# FPGA.net
KiCad netlist of a schematic drawn in Altium Designer
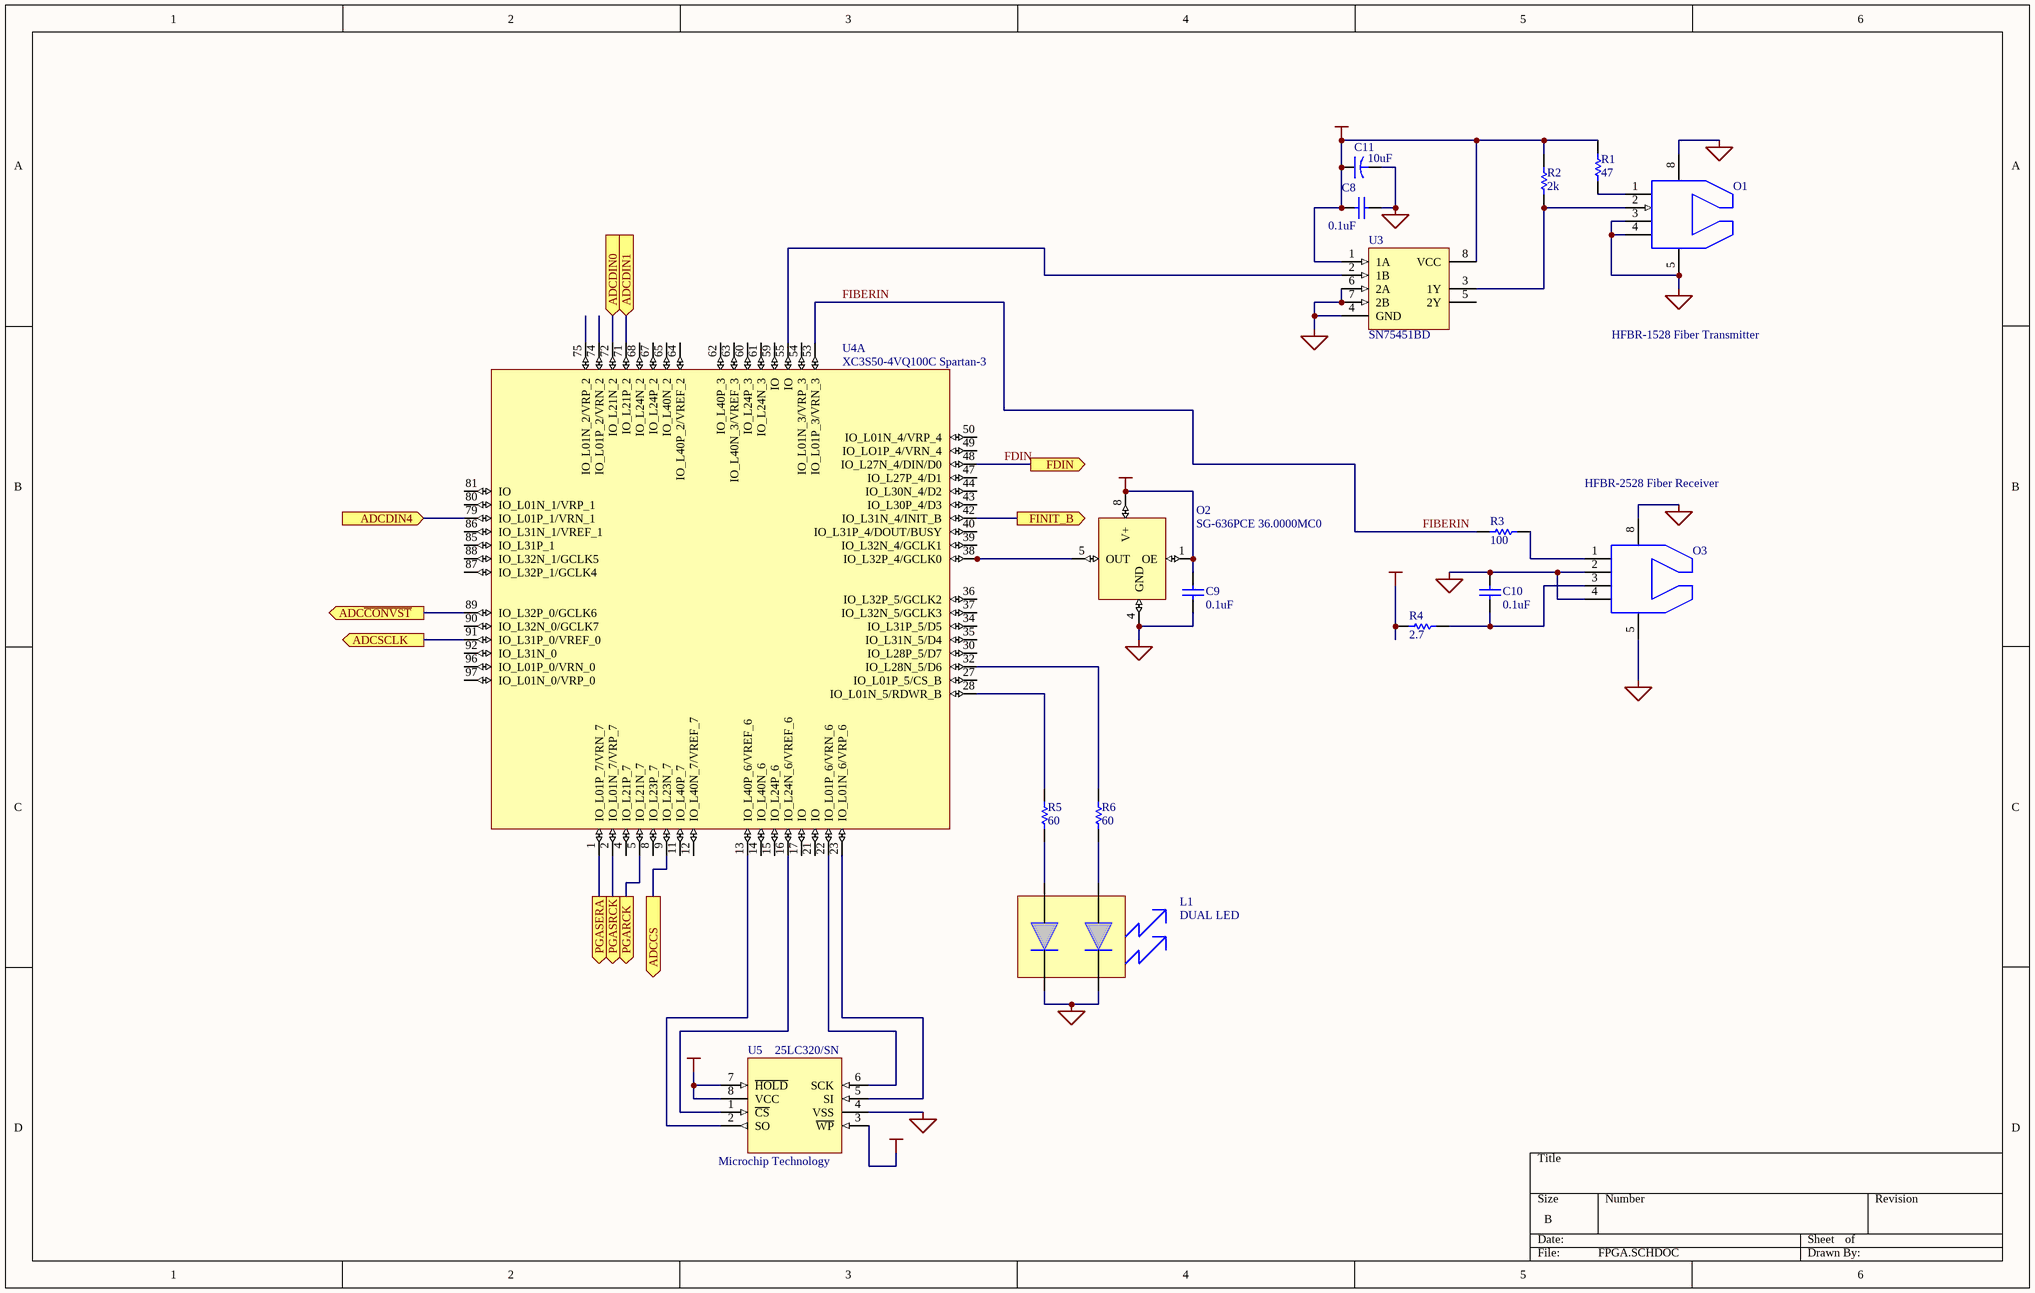
[diagram p0: FPGA.SCHDOC]

(export (version "E")
  (design (tool "Eeschema 10.0.6"))
  (components
    (comp (ref "C8")
      (value "0.1uF")
      (footprint "CC1608-0603")
      (description "Capacitor")
      (fields
        (field (name "MANUFACTURER") "Generic Components")
        (field (name "Comment") "Cap")
        (field (name "PUBLISHER") "Altium Limited")
      )
      (libsource (lib "Miscellaneous Devices") (part "Cap"))
    )
    (comp (ref "C9")
      (value "0.1uF")
      (footprint "CC1608-0603")
      (description "Capacitor")
      (fields
        (field (name "MANUFACTURER") "Generic Components")
        (field (name "Comment") "Cap")
        (field (name "PUBLISHER") "Altium Limited")
      )
      (libsource (lib "Miscellaneous Devices") (part "Cap"))
    )
    (comp (ref "C10")
      (value "0.1uF")
      (footprint "CC1608-0603")
      (description "Capacitor")
      (fields
        (field (name "MANUFACTURER") "Generic Components")
        (field (name "Comment") "Cap")
        (field (name "PUBLISHER") "Altium Limited")
      )
      (libsource (lib "Miscellaneous Devices") (part "Cap"))
    )
    (comp (ref "C11")
      (value "10uF")
      (footprint "TC3528-1411")
      (description "Capacitor")
      (fields (field (name "MANUFACTURER") "Generic Components") (field (name "PUBLISHER") "Altium Limited"))
      (libsource (lib "Miscellaneous Devices") (part "Cap2"))
    )
    (comp (ref "L1")
      (value "DUAL LED")
      (footprint "LUMEX DUAL RT-ANG LED")
      (libsource (lib "parts") (part "DUAL LED"))
    )
    (comp (ref "O1")
      (value "HFBR-1528 Fiber Transmitter")
      (footprint "HPVL")
      (description "Low-cost fiber transmitter")
      (libsource (lib "parts") (part "HFBR-1528"))
    )
    (comp (ref "O2")
      (value "SG-636PCE 36.0000MC0")
      (footprint "SG636PCE")
      (description "Epson CMOS/TTL Oscillator")
      (libsource (lib "parts") (part "SG-636PCE"))
    )
    (comp (ref "O3")
      (value "HFBR-2528 Fiber Receiver")
      (footprint "HPVL")
      (description "Low-cost fiber receiver")
      (libsource (lib "parts") (part "HFBR-2528"))
    )
    (comp (ref "R1")
      (value "47")
      (footprint "CC1608-0603")
      (description "Resistor")
      (fields
        (field (name "MANUFACTURER") "Generic Components")
        (field (name "Comment") "Res1")
        (field (name "PUBLISHER") "Altium Limited")
      )
      (libsource (lib "Miscellaneous Devices") (part "Res1"))
    )
    (comp (ref "R2")
      (value "2k")
      (footprint "CC1608-0603")
      (description "Resistor")
      (fields
        (field (name "MANUFACTURER") "Generic Components")
        (field (name "Comment") "Res1")
        (field (name "PUBLISHER") "Altium Limited")
      )
      (libsource (lib "Miscellaneous Devices") (part "Res1"))
    )
    (comp (ref "R3")
      (value "100")
      (footprint "CC1608-0603")
      (description "Resistor")
      (fields
        (field (name "MANUFACTURER") "Generic Components")
        (field (name "Comment") "Res1")
        (field (name "PUBLISHER") "Altium Limited")
      )
      (libsource (lib "Miscellaneous Devices") (part "Res1"))
    )
    (comp (ref "R4")
      (value "2.7")
      (footprint "CC1608-0603")
      (description "Resistor")
      (fields
        (field (name "MANUFACTURER") "Generic Components")
        (field (name "Comment") "Res1")
        (field (name "PUBLISHER") "Altium Limited")
      )
      (libsource (lib "Miscellaneous Devices") (part "Res1"))
    )
    (comp (ref "R5")
      (value "60")
      (footprint "CC1608-0603")
      (description "Resistor")
      (fields
        (field (name "MANUFACTURER") "Generic Components")
        (field (name "Comment") "Res1")
        (field (name "PUBLISHER") "Altium Limited")
      )
      (libsource (lib "Miscellaneous Devices") (part "Res1"))
    )
    (comp (ref "R6")
      (value "60")
      (footprint "CC1608-0603")
      (description "Resistor")
      (fields
        (field (name "MANUFACTURER") "Generic Components")
        (field (name "Comment") "Res1")
        (field (name "PUBLISHER") "Altium Limited")
      )
      (libsource (lib "Miscellaneous Devices") (part "Res1"))
    )
    (comp (ref "U3")
      (value "SN75451BD")
      (footprint "SO-G8/E2.5")
      (description "Dual Peripheral Driver")
      (fields (field (name "MANUFACTURER") "Texas Instruments") (field (name "PUBLISHER") "Altium Limited"))
      (libsource (lib "TI Interface Peripheral Driver") (part "SN75451BD"))
    )
    (comp (ref "U4")
      (value "XC3S50-4VQ100C Spartan-3")
      (footprint "F-QFP14X14-G100/N")
      (description "Xilinx Spartan-3 VQ100")
      (libsource (lib "parts") (part "XC3S50-4VQ100C"))
    )
    (comp (ref "U5")
      (value "25LC320/SN")
      (footprint "SO-G8/E2.9")
      (description "32k SPI Bus Serial EEPROM")
      (fields (field (name "VENDOR") "Microchip Technology"))
      (libsource (lib "parts") (part "25LC320-SOIC"))
    )
  )
  (nets
    (net (code "1") (name "+5VCC") (class "Default")
      (node (ref "C11") (pin "1") (pinfunction "1_1") (pintype "passive"))
      (node (ref "C8") (pin "1") (pinfunction "1_1") (pintype "passive"))
      (node (ref "R1") (pin "2") (pinfunction "2_2") (pintype "passive"))
      (node (ref "R2") (pin "2") (pinfunction "2_2") (pintype "passive"))
      (node (ref "R4") (pin "1") (pinfunction "1_1") (pintype "passive"))
      (node (ref "U3") (pin "1") (pinfunction "1A_1") (pintype "input"))
      (node (ref "U3") (pin "8") (pinfunction "VCC_8") (pintype "power_in"))
    )
    (net (code "2") (name "/ADCCS") (class "Default")
      (node (ref "U4") (pin "9") (pinfunction "IO_L23N_7_9") (pintype "bidirectional"))
    )
    (net (code "3") (name "/ADCDIN0") (class "Default")
      (node (ref "U4") (pin "72") (pinfunction "IO_L21N_2_72") (pintype "bidirectional"))
    )
    (net (code "4") (name "/ADCDIN1") (class "Default")
      (node (ref "U4") (pin "71") (pinfunction "IO_L21P_2_71") (pintype "bidirectional"))
    )
    (net (code "5") (name "/ADCDIN4") (class "Default")
      (node (ref "U4") (pin "79") (pinfunction "IO_L01P_1/VRN_1_79") (pintype "bidirectional"))
    )
    (net (code "6") (name "/ADCSCLK") (class "Default")
      (node (ref "U4") (pin "91") (pinfunction "IO_L31P_0/VREF_0_91") (pintype "bidirectional"))
    )
    (net (code "7") (name "/ADC~{CONVST}") (class "Default")
      (node (ref "U4") (pin "89") (pinfunction "IO_L32P_0/GCLK6_89") (pintype "bidirectional"))
    )
    (net (code "8") (name "/FDIN") (class "Default")
      (node (ref "U4") (pin "48") (pinfunction "IO_L27N_4/DIN/D0_48") (pintype "bidirectional"))
    )
    (net (code "9") (name "/FIBERIN") (class "Default")
      (node (ref "R3") (pin "1") (pinfunction "1_1") (pintype "passive"))
      (node (ref "U4") (pin "53") (pinfunction "IO_L01P_3/VRN_3_53") (pintype "bidirectional"))
    )
    (net (code "10") (name "/FINIT_B") (class "Default")
      (node (ref "U4") (pin "42") (pinfunction "IO_L31N_4/INIT_B_42") (pintype "bidirectional"))
    )
    (net (code "11") (name "/PGARCK") (class "Default")
      (node (ref "U4") (pin "5") (pinfunction "IO_L21N_7_5") (pintype "bidirectional"))
    )
    (net (code "12") (name "/PGASERA") (class "Default")
      (node (ref "U4") (pin "1") (pinfunction "IO_L01P_7/VRN_7_1") (pintype "bidirectional"))
    )
    (net (code "13") (name "/PGASRCK") (class "Default")
      (node (ref "U4") (pin "2") (pinfunction "IO_L01N_7/VRP_7_2") (pintype "bidirectional"))
    )
    (net (code "14") (name "GND") (class "Default")
      (node (ref "C10") (pin "2") (pinfunction "2_2") (pintype "passive"))
      (node (ref "C11") (pin "2") (pinfunction "2_2") (pintype "passive"))
      (node (ref "C8") (pin "2") (pinfunction "2_2") (pintype "passive"))
      (node (ref "C9") (pin "2") (pinfunction "2_2") (pintype "passive"))
      (node (ref "L1") (pin "2") (pinfunction "2_2") (pintype "passive"))
      (node (ref "L1") (pin "4") (pinfunction "C2_4") (pintype "passive"))
      (node (ref "O1") (pin "3") (pintype "power_in"))
      (node (ref "O1") (pin "4") (pintype "power_in"))
      (node (ref "O1") (pin "5") (pintype "power_in"))
      (node (ref "O1") (pin "8") (pintype "power_in"))
      (node (ref "O2") (pin "4") (pinfunction "GND_4") (pintype "bidirectional"))
      (node (ref "O3") (pin "2") (pintype "power_in"))
      (node (ref "O3") (pin "4") (pintype "power_in"))
      (node (ref "O3") (pin "5") (pintype "power_in"))
      (node (ref "O3") (pin "8") (pintype "power_in"))
      (node (ref "U3") (pin "4") (pinfunction "GND_4") (pintype "power_in"))
      (node (ref "U3") (pin "6") (pinfunction "2A_6") (pintype "input"))
      (node (ref "U3") (pin "7") (pinfunction "2B_7") (pintype "input"))
      (node (ref "U5") (pin "4") (pinfunction "VSS_4") (pintype "power_in"))
    )
    (net (code "15") (name "Net-(C10-Pad1)") (class "Default")
      (node (ref "C10") (pin "1") (pinfunction "1_1") (pintype "passive"))
      (node (ref "O3") (pin "3") (pintype "power_in"))
      (node (ref "R4") (pin "2") (pinfunction "2_2") (pintype "passive"))
    )
    (net (code "16") (name "Net-(L1-A1)") (class "Default")
      (node (ref "L1") (pin "1") (pinfunction "A1_1") (pintype "passive"))
      (node (ref "R5") (pin "2") (pinfunction "2_2") (pintype "passive"))
    )
    (net (code "17") (name "Net-(L1-A2)") (class "Default")
      (node (ref "L1") (pin "3") (pinfunction "A2_3") (pintype "passive"))
      (node (ref "R6") (pin "2") (pinfunction "2_2") (pintype "passive"))
    )
    (net (code "18") (name "Net-(O1-Pad1)") (class "Default")
      (node (ref "O1") (pin "1") (pintype "power_in"))
      (node (ref "R1") (pin "1") (pinfunction "1_1") (pintype "passive"))
    )
    (net (code "19") (name "Net-(O2-OUT)") (class "Default")
      (node (ref "O2") (pin "5") (pinfunction "OUT_5") (pintype "bidirectional"))
      (node (ref "U4") (pin "38") (pinfunction "IO_L32P_4/GCLK0_38") (pintype "bidirectional"))
    )
    (net (code "20") (name "Net-(O3-Pad1)") (class "Default")
      (node (ref "O3") (pin "1") (pintype "power_in"))
      (node (ref "R3") (pin "2") (pinfunction "2_2") (pintype "passive"))
    )
    (net (code "21") (name "Net-(U3-1B)") (class "Default")
      (node (ref "U3") (pin "2") (pinfunction "1B_2") (pintype "input"))
      (node (ref "U4") (pin "55") (pinfunction "IO_55") (pintype "bidirectional"))
    )
    (net (code "22") (name "Net-(U3-1Y)") (class "Default")
      (node (ref "O1") (pin "2") (pintype "input"))
      (node (ref "R2") (pin "1") (pinfunction "1_1") (pintype "passive"))
      (node (ref "U3") (pin "3") (pinfunction "1Y_3") (pintype "open_collector"))
    )
    (net (code "23") (name "Net-(U4A-IO_L01N_5{slash}RDWR_B)") (class "Default")
      (node (ref "R5") (pin "1") (pinfunction "1_1") (pintype "passive"))
      (node (ref "U4") (pin "28") (pinfunction "IO_L01N_5/RDWR_B_28") (pintype "bidirectional"))
    )
    (net (code "24") (name "Net-(U4A-IO_L01N_6{slash}VRP_6)") (class "Default")
      (node (ref "U4") (pin "23") (pinfunction "IO_L01N_6/VRP_6_23") (pintype "bidirectional"))
      (node (ref "U5") (pin "5") (pinfunction "SI_5") (pintype "input"))
    )
    (net (code "25") (name "Net-(U4A-IO_L01P_6{slash}VRN_6)") (class "Default")
      (node (ref "U4") (pin "22") (pinfunction "IO_L01P_6/VRN_6_22") (pintype "bidirectional"))
      (node (ref "U5") (pin "6") (pinfunction "SCK_6") (pintype "input"))
    )
    (net (code "26") (name "Net-(U4A-IO_L24N_6{slash}VREF_6)") (class "Default")
      (node (ref "U4") (pin "16") (pinfunction "IO_L24N_6/VREF_6_16") (pintype "bidirectional"))
      (node (ref "U5") (pin "1") (pinfunction "~{CS}_1") (pintype "input"))
    )
    (net (code "27") (name "Net-(U4A-IO_L28N_5{slash}D6)") (class "Default")
      (node (ref "R6") (pin "1") (pinfunction "1_1") (pintype "passive"))
      (node (ref "U4") (pin "32") (pinfunction "IO_L28N_5/D6_32") (pintype "bidirectional"))
    )
    (net (code "28") (name "Net-(U4A-IO_L40P_6{slash}VREF_6)") (class "Default")
      (node (ref "U4") (pin "13") (pinfunction "IO_L40P_6/VREF_6_13") (pintype "bidirectional"))
      (node (ref "U5") (pin "2") (pinfunction "SO_2") (pintype "output"))
    )
    (net (code "29") (name "VCC") (class "Default")
      (node (ref "C9") (pin "1") (pinfunction "1_1") (pintype "passive"))
      (node (ref "O2") (pin "1") (pinfunction "OE_1") (pintype "bidirectional"))
      (node (ref "O2") (pin "8") (pinfunction "V+_8") (pintype "bidirectional"))
      (node (ref "U5") (pin "3") (pinfunction "~{WP}_3") (pintype "input"))
      (node (ref "U5") (pin "7") (pinfunction "~{HOLD}_7") (pintype "input"))
      (node (ref "U5") (pin "8") (pinfunction "VCC_8") (pintype "power_in"))
    )
    (net (code "30") (name "unconnected-(U3-2Y-Pad5)") (class "Default")
      (node (ref "U3") (pin "5") (pinfunction "2Y_5") (pintype "open_collector"))
    )
    (net (code "31") (name "unconnected-(U4A-IO-Pad17)") (class "Default")
      (node (ref "U4") (pin "17") (pinfunction "IO_17") (pintype "bidirectional"))
    )
    (net (code "32") (name "unconnected-(U4A-IO-Pad21)") (class "Default")
      (node (ref "U4") (pin "21") (pinfunction "IO_21") (pintype "bidirectional"))
    )
    (net (code "33") (name "unconnected-(U4A-IO-Pad59)") (class "Default")
      (node (ref "U4") (pin "59") (pinfunction "IO_59") (pintype "bidirectional"))
    )
    (net (code "34") (name "unconnected-(U4A-IO-Pad81)") (class "Default")
      (node (ref "U4") (pin "81") (pinfunction "IO_81") (pintype "bidirectional"))
    )
    (net (code "35") (name "unconnected-(U4A-IO_L01N_0{slash}VRP_0-Pad97)") (class "Default")
      (node (ref "U4") (pin "97") (pinfunction "IO_L01N_0/VRP_0_97") (pintype "bidirectional"))
    )
    (net (code "36") (name "unconnected-(U4A-IO_L01N_1{slash}VRP_1-Pad80)") (class "Default")
      (node (ref "U4") (pin "80") (pinfunction "IO_L01N_1/VRP_1_80") (pintype "bidirectional"))
    )
    (net (code "37") (name "unconnected-(U4A-IO_L01N_2{slash}VRP_2-Pad75)") (class "Default")
      (node (ref "U4") (pin "75") (pinfunction "IO_L01N_2/VRP_2_75") (pintype "bidirectional"))
    )
    (net (code "38") (name "unconnected-(U4A-IO_L01N_3{slash}VRP_3-Pad54)") (class "Default")
      (node (ref "U4") (pin "54") (pinfunction "IO_L01N_3/VRP_3_54") (pintype "bidirectional"))
    )
    (net (code "39") (name "unconnected-(U4A-IO_L01N_4{slash}VRP_4-Pad50)") (class "Default")
      (node (ref "U4") (pin "50") (pinfunction "IO_L01N_4/VRP_4_50") (pintype "bidirectional"))
    )
    (net (code "40") (name "unconnected-(U4A-IO_L01P_0{slash}VRN_0-Pad96)") (class "Default")
      (node (ref "U4") (pin "96") (pinfunction "IO_L01P_0/VRN_0_96") (pintype "bidirectional"))
    )
    (net (code "41") (name "unconnected-(U4A-IO_L01P_2{slash}VRN_2-Pad74)") (class "Default")
      (node (ref "U4") (pin "74") (pinfunction "IO_L01P_2/VRN_2_74") (pintype "bidirectional"))
    )
    (net (code "42") (name "unconnected-(U4A-IO_L01P_5{slash}CS_B-Pad27)") (class "Default")
      (node (ref "U4") (pin "27") (pinfunction "IO_L01P_5/CS_B_27") (pintype "bidirectional"))
    )
    (net (code "43") (name "unconnected-(U4A-IO_L21P_7-Pad4)") (class "Default")
      (node (ref "U4") (pin "4") (pinfunction "IO_L21P_7_4") (pintype "bidirectional"))
    )
    (net (code "44") (name "unconnected-(U4A-IO_L23P_7-Pad8)") (class "Default")
      (node (ref "U4") (pin "8") (pinfunction "IO_L23P_7_8") (pintype "bidirectional"))
    )
    (net (code "45") (name "unconnected-(U4A-IO_L24N_2-Pad68)") (class "Default")
      (node (ref "U4") (pin "68") (pinfunction "IO_L24N_2_68") (pintype "bidirectional"))
    )
    (net (code "46") (name "unconnected-(U4A-IO_L24N_3-Pad61)") (class "Default")
      (node (ref "U4") (pin "61") (pinfunction "IO_L24N_3_61") (pintype "bidirectional"))
    )
    (net (code "47") (name "unconnected-(U4A-IO_L24P_2-Pad67)") (class "Default")
      (node (ref "U4") (pin "67") (pinfunction "IO_L24P_2_67") (pintype "bidirectional"))
    )
    (net (code "48") (name "unconnected-(U4A-IO_L24P_3-Pad60)") (class "Default")
      (node (ref "U4") (pin "60") (pinfunction "IO_L24P_3_60") (pintype "bidirectional"))
    )
    (net (code "49") (name "unconnected-(U4A-IO_L24P_6-Pad15)") (class "Default")
      (node (ref "U4") (pin "15") (pinfunction "IO_L24P_6_15") (pintype "bidirectional"))
    )
    (net (code "50") (name "unconnected-(U4A-IO_L27P_4{slash}D1-Pad47)") (class "Default")
      (node (ref "U4") (pin "47") (pinfunction "IO_L27P_4/D1_47") (pintype "bidirectional"))
    )
    (net (code "51") (name "unconnected-(U4A-IO_L28P_5{slash}D7-Pad30)") (class "Default")
      (node (ref "U4") (pin "30") (pinfunction "IO_L28P_5/D7_30") (pintype "bidirectional"))
    )
    (net (code "52") (name "unconnected-(U4A-IO_L30N_4{slash}D2-Pad44)") (class "Default")
      (node (ref "U4") (pin "44") (pinfunction "IO_L30N_4/D2_44") (pintype "bidirectional"))
    )
    (net (code "53") (name "unconnected-(U4A-IO_L30P_4{slash}D3-Pad43)") (class "Default")
      (node (ref "U4") (pin "43") (pinfunction "IO_L30P_4/D3_43") (pintype "bidirectional"))
    )
    (net (code "54") (name "unconnected-(U4A-IO_L31N_0-Pad92)") (class "Default")
      (node (ref "U4") (pin "92") (pinfunction "IO_L31N_0_92") (pintype "bidirectional"))
    )
    (net (code "55") (name "unconnected-(U4A-IO_L31N_1{slash}VREF_1-Pad86)") (class "Default")
      (node (ref "U4") (pin "86") (pinfunction "IO_L31N_1/VREF_1_86") (pintype "bidirectional"))
    )
    (net (code "56") (name "unconnected-(U4A-IO_L31N_5{slash}D4-Pad35)") (class "Default")
      (node (ref "U4") (pin "35") (pinfunction "IO_L31N_5/D4_35") (pintype "bidirectional"))
    )
    (net (code "57") (name "unconnected-(U4A-IO_L31P_1-Pad85)") (class "Default")
      (node (ref "U4") (pin "85") (pinfunction "IO_L31P_1_85") (pintype "bidirectional"))
    )
    (net (code "58") (name "unconnected-(U4A-IO_L31P_4{slash}DOUT{slash}BUSY-Pad40)") (class "Default")
      (node (ref "U4") (pin "40") (pinfunction "IO_L31P_4/DOUT/BUSY_40") (pintype "bidirectional"))
    )
    (net (code "59") (name "unconnected-(U4A-IO_L31P_5{slash}D5-Pad34)") (class "Default")
      (node (ref "U4") (pin "34") (pinfunction "IO_L31P_5/D5_34") (pintype "bidirectional"))
    )
    (net (code "60") (name "unconnected-(U4A-IO_L32N_0{slash}GCLK7-Pad90)") (class "Default")
      (node (ref "U4") (pin "90") (pinfunction "IO_L32N_0/GCLK7_90") (pintype "bidirectional"))
    )
    (net (code "61") (name "unconnected-(U4A-IO_L32N_1{slash}GCLK5-Pad88)") (class "Default")
      (node (ref "U4") (pin "88") (pinfunction "IO_L32N_1/GCLK5_88") (pintype "bidirectional"))
    )
    (net (code "62") (name "unconnected-(U4A-IO_L32N_4{slash}GCLK1-Pad39)") (class "Default")
      (node (ref "U4") (pin "39") (pinfunction "IO_L32N_4/GCLK1_39") (pintype "bidirectional"))
    )
    (net (code "63") (name "unconnected-(U4A-IO_L32N_5{slash}GCLK3-Pad37)") (class "Default")
      (node (ref "U4") (pin "37") (pinfunction "IO_L32N_5/GCLK3_37") (pintype "bidirectional"))
    )
    (net (code "64") (name "unconnected-(U4A-IO_L32P_1{slash}GCLK4-Pad87)") (class "Default")
      (node (ref "U4") (pin "87") (pinfunction "IO_L32P_1/GCLK4_87") (pintype "bidirectional"))
    )
    (net (code "65") (name "unconnected-(U4A-IO_L32P_5{slash}GCLK2-Pad36)") (class "Default")
      (node (ref "U4") (pin "36") (pinfunction "IO_L32P_5/GCLK2_36") (pintype "bidirectional"))
    )
    (net (code "66") (name "unconnected-(U4A-IO_L40N_2-Pad65)") (class "Default")
      (node (ref "U4") (pin "65") (pinfunction "IO_L40N_2_65") (pintype "bidirectional"))
    )
    (net (code "67") (name "unconnected-(U4A-IO_L40N_3{slash}VREF_3-Pad63)") (class "Default")
      (node (ref "U4") (pin "63") (pinfunction "IO_L40N_3/VREF_3_63") (pintype "bidirectional"))
    )
    (net (code "68") (name "unconnected-(U4A-IO_L40N_6-Pad14)") (class "Default")
      (node (ref "U4") (pin "14") (pinfunction "IO_L40N_6_14") (pintype "bidirectional"))
    )
    (net (code "69") (name "unconnected-(U4A-IO_L40N_7{slash}VREF_7-Pad12)") (class "Default")
      (node (ref "U4") (pin "12") (pinfunction "IO_L40N_7/VREF_7_12") (pintype "bidirectional"))
    )
    (net (code "70") (name "unconnected-(U4A-IO_L40P_2{slash}VREF_2-Pad64)") (class "Default")
      (node (ref "U4") (pin "64") (pinfunction "IO_L40P_2/VREF_2_64") (pintype "bidirectional"))
    )
    (net (code "71") (name "unconnected-(U4A-IO_L40P_3-Pad62)") (class "Default")
      (node (ref "U4") (pin "62") (pinfunction "IO_L40P_3_62") (pintype "bidirectional"))
    )
    (net (code "72") (name "unconnected-(U4A-IO_L40P_7-Pad11)") (class "Default")
      (node (ref "U4") (pin "11") (pinfunction "IO_L40P_7_11") (pintype "bidirectional"))
    )
    (net (code "73") (name "unconnected-(U4A-IO_LO1P_4{slash}VRN_4-Pad49)") (class "Default")
      (node (ref "U4") (pin "49") (pinfunction "IO_LO1P_4/VRN_4_49") (pintype "bidirectional"))
    )
  )
)
